# SCH_555_Timer_PWM_Compact_2022-07-11.net
KiCad netlist of a schematic drawn in EasyEDA
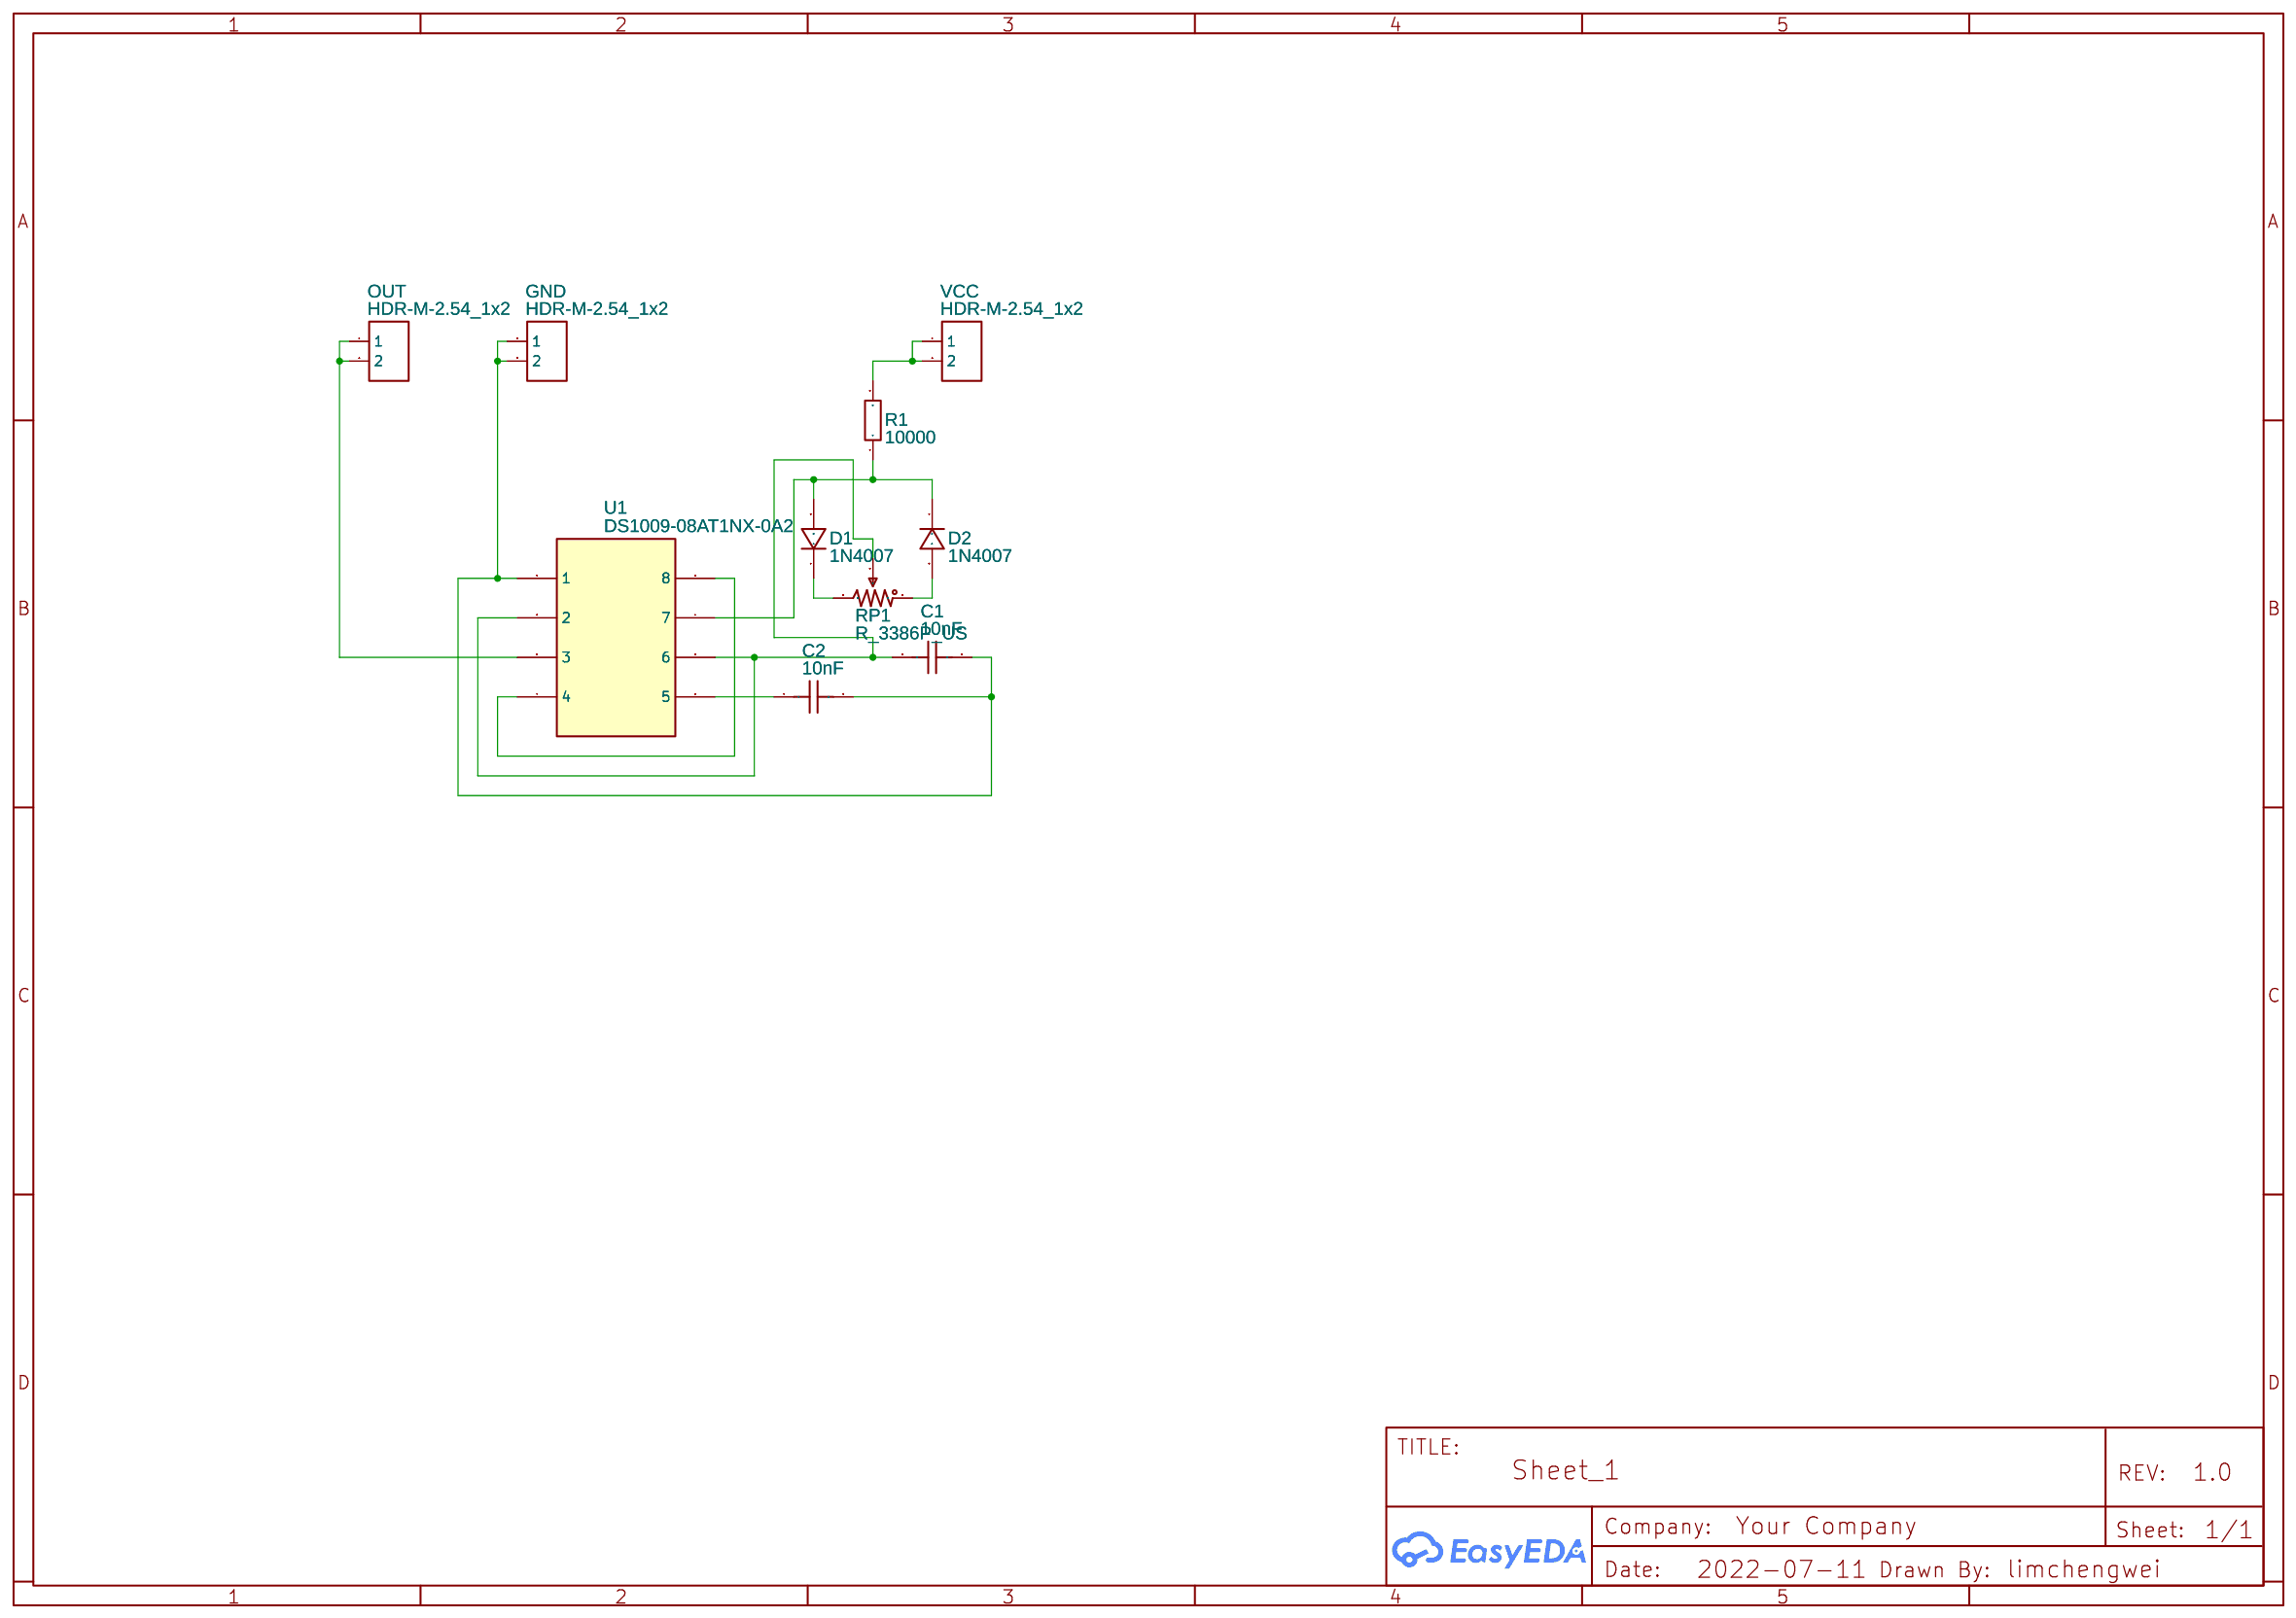
[diagram p0: schematic sheet]

(export (version "E")
  (design (tool "Eeschema 10.0.6"))
  (components
    (comp (ref "C1")
      (value "10nF")
      (fields
        (field (name "BOM_Manufacturer Part") "CC1H103MC76DB45A30S8")
        (field (name "BOM_Supplier Part") "C377837")
      )
      (libsource (lib "") (part "CC1H103MC76DB45A30S8"))
    )
    (comp (ref "C2")
      (value "10nF")
      (fields
        (field (name "BOM_Manufacturer Part") "CC1H103MC76DB45A30S8")
        (field (name "BOM_Supplier Part") "C377837")
      )
      (libsource (lib "") (part "CC1H103MC76DB45A30S8"))
    )
    (comp (ref "D1")
      (value "1N4007")
      (fields (field (name "BOM_Supplier Part") "C106903"))
      (libsource (lib "") (part "1N4007"))
    )
    (comp (ref "D2")
      (value "1N4007")
      (fields (field (name "BOM_Supplier Part") "C106903"))
      (libsource (lib "") (part "1N4007_1"))
    )
    (comp (ref "GND")
      (value "HDR-M-2.54_1x2")
      (fields (field (name "BOM_Supplier Part") "C124375"))
      (libsource (lib "") (part "HDR-M-2.54_1x2"))
    )
    (comp (ref "OUT")
      (value "HDR-M-2.54_1x2")
      (fields (field (name "BOM_Supplier Part") "C124375"))
      (libsource (lib "") (part "HDR-M-2.54_1x2_1"))
    )
    (comp (ref "R1")
      (value "10000")
      (fields (field (name "BOM_Supplier Part") "C119312"))
      (libsource (lib "") (part "MF1/4W-300Ω±1% T52"))
    )
    (comp (ref "RP1") (value "R_3386P_US") (libsource (lib "") (part "R_3386P_US")))
    (comp (ref "U1")
      (value "DS1009-08AT1NX-0A2")
      (fields (field (name "BOM_Supplier Part") "C72124"))
      (libsource (lib "") (part "DS1009-08AT1NX-0A2"))
    )
    (comp (ref "VCC")
      (value "HDR-M-2.54_1x2")
      (fields (field (name "BOM_Supplier Part") "C124375"))
      (libsource (lib "") (part "HDR-M-2.54_1x2_2"))
    )
  )
  (nets
    (net (code "1") (name "Net-(C1-Pad1)") (class "Default")
      (node (ref "C1") (pin "1") (pinfunction "1_1") (pintype "unspecified"))
      (node (ref "RP1") (pin "2") (pinfunction "2_2") (pintype "unspecified"))
      (node (ref "U1") (pin "2") (pinfunction "2_2") (pintype "input"))
      (node (ref "U1") (pin "6") (pinfunction "6_6") (pintype "input"))
    )
    (net (code "2") (name "Net-(C1-Pad2)") (class "Default")
      (node (ref "C1") (pin "2") (pinfunction "2_2") (pintype "unspecified"))
      (node (ref "C2") (pin "2") (pinfunction "2_2") (pintype "unspecified"))
      (node (ref "GND") (pin "1") (pinfunction "1_1") (pintype "unspecified"))
      (node (ref "GND") (pin "2") (pinfunction "2_2") (pintype "unspecified"))
      (node (ref "U1") (pin "1") (pinfunction "1_1") (pintype "input"))
    )
    (net (code "3") (name "Net-(C2-Pad1)") (class "Default")
      (node (ref "C2") (pin "1") (pinfunction "1_1") (pintype "unspecified"))
      (node (ref "U1") (pin "5") (pinfunction "5_5") (pintype "input"))
    )
    (net (code "4") (name "Net-(D1-Pad1)") (class "Default")
      (node (ref "D1") (pin "1") (pinfunction "1_1") (pintype "unspecified"))
      (node (ref "RP1") (pin "3") (pinfunction "3_3") (pintype "unspecified"))
    )
    (net (code "5") (name "Net-(D1-Pad2)") (class "Default")
      (node (ref "D1") (pin "2") (pinfunction "2_2") (pintype "unspecified"))
      (node (ref "D2") (pin "1") (pinfunction "1_1") (pintype "unspecified"))
      (node (ref "R1") (pin "1") (pinfunction "1_1") (pintype "unspecified"))
      (node (ref "U1") (pin "7") (pinfunction "7_7") (pintype "input"))
    )
    (net (code "6") (name "Net-(D2-Pad2)") (class "Default")
      (node (ref "D2") (pin "2") (pinfunction "2_2") (pintype "unspecified"))
      (node (ref "RP1") (pin "1") (pinfunction "1_1") (pintype "unspecified"))
    )
    (net (code "7") (name "Net-(OUT-Pad1)") (class "Default")
      (node (ref "OUT") (pin "1") (pinfunction "1_1") (pintype "unspecified"))
      (node (ref "OUT") (pin "2") (pinfunction "2_2") (pintype "unspecified"))
      (node (ref "U1") (pin "3") (pinfunction "3_3") (pintype "input"))
    )
    (net (code "8") (name "Net-(R1-Pad2)") (class "Default")
      (node (ref "R1") (pin "2") (pinfunction "2_2") (pintype "unspecified"))
      (node (ref "VCC") (pin "1") (pinfunction "1_1") (pintype "unspecified"))
      (node (ref "VCC") (pin "2") (pinfunction "2_2") (pintype "unspecified"))
    )
    (net (code "9") (name "Net-(U1-Pad4)") (class "Default")
      (node (ref "U1") (pin "4") (pinfunction "4_4") (pintype "input"))
      (node (ref "U1") (pin "8") (pinfunction "8_8") (pintype "input"))
    )
  )
)
